# Chameleon-Mini-RevE-3.net
KiCad netlist of a schematic drawn in EAGLE
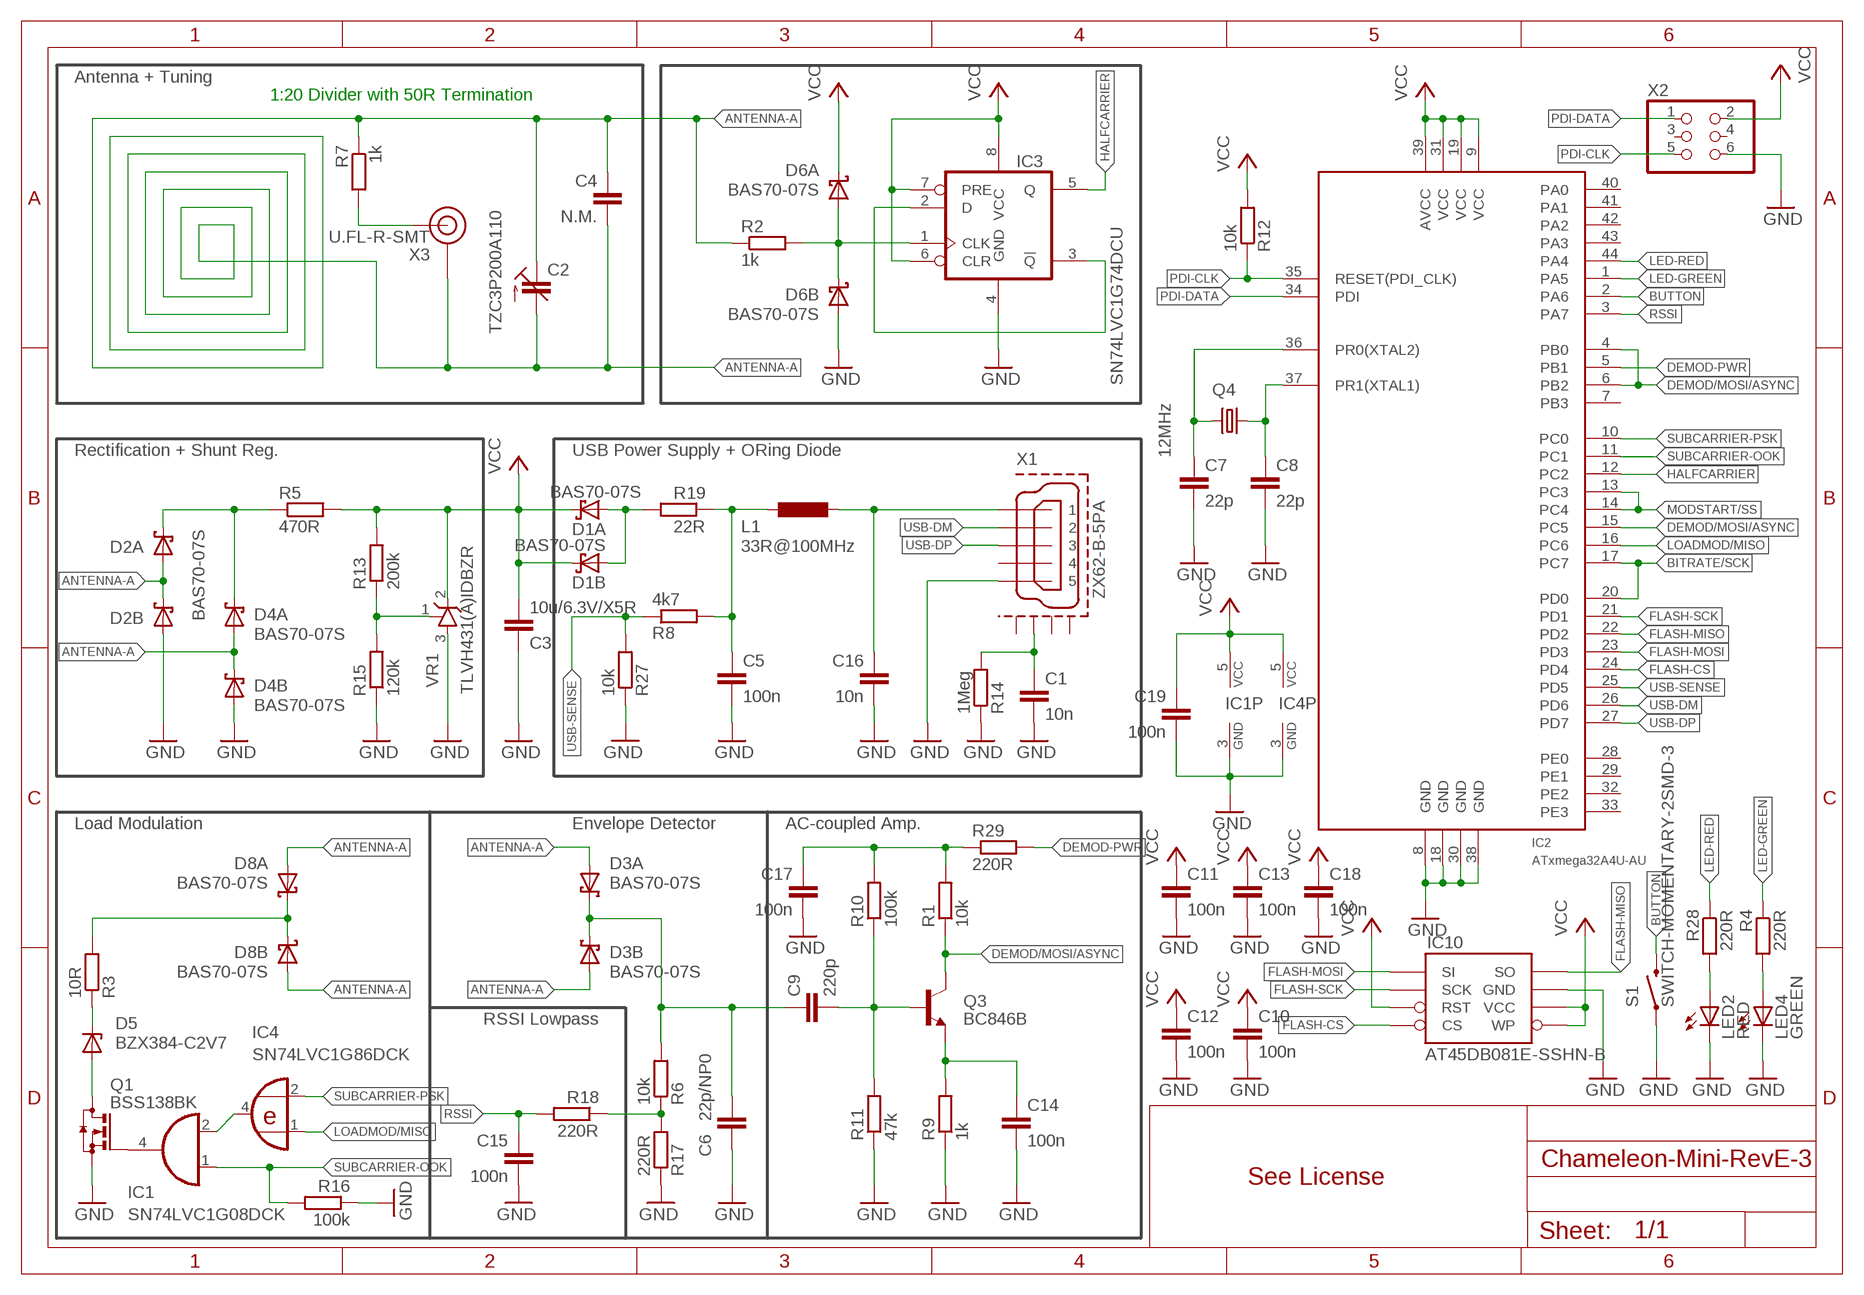
[diagram p0: schematic, sheet 1]

(export (version "E")
  (design (tool "Eeschema 10.0.6"))
  (components
    (comp (ref "C1")
      (value "10n")
      (footprint "eagle-import:C1206K")
      (libsource (lib "eagle-import") (part "C-EUC1206K"))
    )
    (comp (ref "C2")
      (value "TZC3P200A110")
      (footprint "eagle-import:TZC3P")
      (libsource (lib "eagle-import") (part "TZC3P"))
    )
    (comp (ref "C3")
      (value "10u/6.3V/X5R")
      (footprint "eagle-import:C1206K")
      (libsource (lib "eagle-import") (part "C-EUC1206K"))
    )
    (comp (ref "C4")
      (value "N.M.")
      (footprint "eagle-import:C1206")
      (libsource (lib "eagle-import") (part "C-EUC1206"))
    )
    (comp (ref "C5")
      (value "100n")
      (footprint "eagle-import:C1206K")
      (libsource (lib "eagle-import") (part "C-EUC1206K"))
    )
    (comp (ref "C6")
      (value "22p/NP0")
      (footprint "eagle-import:C0603K")
      (libsource (lib "eagle-import") (part "C-EUC0603K"))
    )
    (comp (ref "C7")
      (value "22p")
      (footprint "eagle-import:C0603K")
      (libsource (lib "eagle-import") (part "C-EUC0603K"))
    )
    (comp (ref "C8")
      (value "22p")
      (footprint "eagle-import:C0603K")
      (libsource (lib "eagle-import") (part "C-EUC0603K"))
    )
    (comp (ref "C9")
      (value "220p")
      (footprint "eagle-import:C0603K")
      (libsource (lib "eagle-import") (part "C-EUC0603K"))
    )
    (comp (ref "C10")
      (value "100n")
      (footprint "eagle-import:C0603K")
      (libsource (lib "eagle-import") (part "C-EUC0603K"))
    )
    (comp (ref "C11")
      (value "100n")
      (footprint "eagle-import:C0603K")
      (libsource (lib "eagle-import") (part "C-EUC0603K"))
    )
    (comp (ref "C12")
      (value "100n")
      (footprint "eagle-import:C0603K")
      (libsource (lib "eagle-import") (part "C-EUC0603K"))
    )
    (comp (ref "C13")
      (value "100n")
      (footprint "eagle-import:C0603K")
      (libsource (lib "eagle-import") (part "C-EUC0603K"))
    )
    (comp (ref "C14")
      (value "100n")
      (footprint "eagle-import:C0603K")
      (libsource (lib "eagle-import") (part "C-EUC0603K"))
    )
    (comp (ref "C15")
      (value "100n")
      (footprint "eagle-import:C0603K")
      (libsource (lib "eagle-import") (part "C-EUC0603K"))
    )
    (comp (ref "C16")
      (value "10n")
      (footprint "eagle-import:C1206K")
      (libsource (lib "eagle-import") (part "C-EUC1206K"))
    )
    (comp (ref "C17")
      (value "100n")
      (footprint "eagle-import:C0603K")
      (libsource (lib "eagle-import") (part "C-EUC0603K"))
    )
    (comp (ref "C18")
      (value "100n")
      (footprint "eagle-import:C0603K")
      (libsource (lib "eagle-import") (part "C-EUC0603K"))
    )
    (comp (ref "C19")
      (value "100n")
      (footprint "eagle-import:C0603K")
      (libsource (lib "eagle-import") (part "C-EUC0603K"))
    )
    (comp (ref "D1")
      (value "BAS70-07S")
      (footprint "eagle-import:SOT363_PHILIPS")
      (libsource (lib "eagle-import") (part "BAS70-07S"))
    )
    (comp (ref "D2")
      (value "BAS70-07S")
      (footprint "eagle-import:SOT363_PHILIPS")
      (libsource (lib "eagle-import") (part "BAS70-07S"))
    )
    (comp (ref "D3")
      (value "BAS70-07S")
      (footprint "eagle-import:SOT363_PHILIPS")
      (libsource (lib "eagle-import") (part "BAS70-07S"))
    )
    (comp (ref "D4")
      (value "BAS70-07S")
      (footprint "eagle-import:SOT363_PHILIPS")
      (libsource (lib "eagle-import") (part "BAS70-07S"))
    )
    (comp (ref "D5")
      (value "BZX384-C2V7")
      (footprint "eagle-import:SOD323")
      (libsource (lib "eagle-import") (part "BZX384"))
    )
    (comp (ref "D6")
      (value "BAS70-07S")
      (footprint "eagle-import:SOT363_PHILIPS")
      (libsource (lib "eagle-import") (part "BAS70-07S"))
    )
    (comp (ref "D8")
      (value "BAS70-07S")
      (footprint "eagle-import:SOT363_PHILIPS")
      (libsource (lib "eagle-import") (part "BAS70-07S"))
    )
    (comp (ref "IC1")
      (value "SN74LVC1G08DCK")
      (footprint "eagle-import:SC70-5")
      (libsource (lib "eagle-import") (part "741G08DCKLVC"))
    )
    (comp (ref "IC2")
      (value "ATxmega32A4U-AU")
      (footprint "eagle-import:TQFP44")
      (libsource (lib "eagle-import") (part "ATXMEGA_A4-A"))
    )
    (comp (ref "IC3")
      (value "SN74LVC1G74DCU")
      (footprint "eagle-import:VSSOP8")
      (libsource (lib "eagle-import") (part "74LVC1G74DC"))
    )
    (comp (ref "IC4")
      (value "SN74LVC1G86DCK")
      (footprint "eagle-import:SC70-5")
      (libsource (lib "eagle-import") (part "741G86DCKAHC"))
    )
    (comp (ref "IC10")
      (value "AT45DB081E-SSHN-B")
      (footprint "eagle-import:SO08")
      (libsource (lib "eagle-import") (part "AT45DB041B"))
    )
    (comp (ref "L1")
      (value "33R@100MHz")
      (footprint "eagle-import:L2012C")
      (libsource (lib "eagle-import") (part "L-EUL2012C"))
    )
    (comp (ref "LED2")
      (value "RED")
      (footprint "eagle-import:CHIPLED_0805")
      (libsource (lib "eagle-import") (part "LEDCHIPLED_0805"))
    )
    (comp (ref "LED4")
      (value "GREEN")
      (footprint "eagle-import:CHIPLED_0805")
      (libsource (lib "eagle-import") (part "LEDCHIPLED_0805"))
    )
    (comp (ref "Q1")
      (value "BSS138BK")
      (footprint "eagle-import:SOT23")
      (libsource (lib "eagle-import") (part "BSS123"))
    )
    (comp (ref "Q3")
      (value "BC846B")
      (footprint "eagle-import:SOT23")
      (libsource (lib "eagle-import") (part "BC846SMDB"))
    )
    (comp (ref "Q4")
      (value "12MHz")
      (footprint "eagle-import:5MMX3.2MM")
      (libsource (lib "eagle-import") (part "TXC7B"))
    )
    (comp (ref "R1")
      (value "10k")
      (footprint "eagle-import:R0603")
      (libsource (lib "eagle-import") (part "R-EU_R0603"))
    )
    (comp (ref "R2")
      (value "1k")
      (footprint "eagle-import:R0603")
      (libsource (lib "eagle-import") (part "R-EU_R0603"))
    )
    (comp (ref "R3")
      (value "10R")
      (footprint "eagle-import:R0603")
      (libsource (lib "eagle-import") (part "R-EU_R0603"))
    )
    (comp (ref "R4")
      (value "220R")
      (footprint "eagle-import:R0603")
      (libsource (lib "eagle-import") (part "R-EU_R0603"))
    )
    (comp (ref "R5")
      (value "470R")
      (footprint "eagle-import:R1206")
      (libsource (lib "eagle-import") (part "R-EU_R1206"))
    )
    (comp (ref "R6")
      (value "10k")
      (footprint "eagle-import:R0603")
      (libsource (lib "eagle-import") (part "R-EU_R0603"))
    )
    (comp (ref "R7")
      (value "1k")
      (footprint "eagle-import:R1206")
      (libsource (lib "eagle-import") (part "R-EU_R1206"))
    )
    (comp (ref "R8")
      (value "4k7")
      (footprint "eagle-import:R0603")
      (libsource (lib "eagle-import") (part "R-EU_R0603"))
    )
    (comp (ref "R9")
      (value "1k")
      (footprint "eagle-import:R0603")
      (libsource (lib "eagle-import") (part "R-EU_R0603"))
    )
    (comp (ref "R10")
      (value "100k")
      (footprint "eagle-import:R0603")
      (libsource (lib "eagle-import") (part "R-EU_R0603"))
    )
    (comp (ref "R11")
      (value "47k")
      (footprint "eagle-import:R0603")
      (libsource (lib "eagle-import") (part "R-EU_R0603"))
    )
    (comp (ref "R12")
      (value "10k")
      (footprint "eagle-import:R0603")
      (libsource (lib "eagle-import") (part "R-EU_R0603"))
    )
    (comp (ref "R13")
      (value "200k")
      (footprint "eagle-import:R0603")
      (libsource (lib "eagle-import") (part "R-EU_R0603"))
    )
    (comp (ref "R14")
      (value "1Meg")
      (footprint "eagle-import:R1206")
      (libsource (lib "eagle-import") (part "R-EU_R1206"))
    )
    (comp (ref "R15")
      (value "120k")
      (footprint "eagle-import:R0603")
      (libsource (lib "eagle-import") (part "R-EU_R0603"))
    )
    (comp (ref "R16")
      (value "100k")
      (footprint "eagle-import:R0603")
      (libsource (lib "eagle-import") (part "R-EU_R0603"))
    )
    (comp (ref "R17")
      (value "220R")
      (footprint "eagle-import:R0603")
      (libsource (lib "eagle-import") (part "R-EU_R0603"))
    )
    (comp (ref "R18")
      (value "220R")
      (footprint "eagle-import:R0603")
      (libsource (lib "eagle-import") (part "R-EU_R0603"))
    )
    (comp (ref "R19")
      (value "22R")
      (footprint "eagle-import:R1206")
      (libsource (lib "eagle-import") (part "R-EU_R1206"))
    )
    (comp (ref "R27")
      (value "10k")
      (footprint "eagle-import:R0603")
      (libsource (lib "eagle-import") (part "R-EU_R0603"))
    )
    (comp (ref "R28")
      (value "220R")
      (footprint "eagle-import:R0603")
      (libsource (lib "eagle-import") (part "R-EU_R0603"))
    )
    (comp (ref "R29")
      (value "220R")
      (footprint "eagle-import:R0603")
      (libsource (lib "eagle-import") (part "R-EU_R0603"))
    )
    (comp (ref "S1")
      (value "SWITCH-MOMENTARY-2SMD-3")
      (footprint "eagle-import:TACTILE_SWITCH_SMD-3")
      (libsource (lib "eagle-import") (part "SWITCH-MOMENTARY-2SMD-3"))
    )
    (comp (ref "VR1")
      (value "TLVH431(A)IDBZR")
      (footprint "eagle-import:SOT23")
      (libsource (lib "eagle-import") (part "TLVH431-SOT23"))
    )
    (comp (ref "X1")
      (value "ZX62-B-5PA")
      (footprint "eagle-import:ZX62-B-5PA-LONG")
      (libsource (lib "eagle-import") (part "ZX62-B-5PA-LONG"))
    )
    (comp (ref "X2")
      (value "PINHD-2X3-2.54-EDGE")
      (footprint "eagle-import:PINHD-2X3-2.54-EDGE")
      (libsource (lib "eagle-import") (part "PINHD-2X3-2.54-EDGE"))
    )
    (comp (ref "X3")
      (value "U.FL-R-SMT")
      (footprint "eagle-import:U.FL-R-SMT")
      (libsource (lib "eagle-import") (part "U.FL-R-SMT"))
    )
  )
  (nets
    (net (code "1") (name "ANTENNA-A") (class "Default")
      (node (ref "C2") (pin "1") (pinfunction "A_1") (pintype "passive"))
      (node (ref "C2") (pin "2") (pinfunction "E_2") (pintype "passive"))
      (node (ref "C4") (pin "1") (pinfunction "1_1") (pintype "passive"))
      (node (ref "C4") (pin "2") (pinfunction "2_2") (pintype "passive"))
      (node (ref "D2") (pin "1") (pinfunction "A_1") (pintype "passive"))
      (node (ref "D2") (pin "3") (pinfunction "C_3") (pintype "passive"))
      (node (ref "D3") (pin "1") (pinfunction "A_1") (pintype "passive"))
      (node (ref "D3") (pin "4") (pinfunction "A_4") (pintype "passive"))
      (node (ref "D4") (pin "1") (pinfunction "A_1") (pintype "passive"))
      (node (ref "D4") (pin "3") (pinfunction "C_3") (pintype "passive"))
      (node (ref "D8") (pin "1") (pinfunction "A_1") (pintype "passive"))
      (node (ref "D8") (pin "4") (pinfunction "A_4") (pintype "passive"))
      (node (ref "R2") (pin "1") (pinfunction "1_1") (pintype "passive"))
      (node (ref "R7") (pin "1") (pinfunction "1_1") (pintype "passive"))
      (node (ref "X3") (pin "GND2") (pinfunction "GND_GND2") (pintype "bidirectional"))
    )
    (net (code "2") (name "BITRATE{slash}SCK") (class "Default")
      (node (ref "IC2") (pin "17") (pinfunction "PC7_17") (pintype "bidirectional"))
      (node (ref "IC2") (pin "20") (pinfunction "PD0_20") (pintype "bidirectional"))
    )
    (net (code "3") (name "BUTTON") (class "Default")
      (node (ref "IC2") (pin "2") (pinfunction "PA6_2") (pintype "bidirectional"))
      (node (ref "S1") (pin "4") (pinfunction "2_4") (pintype "passive"))
    )
    (net (code "4") (name "DEMOD-PWR") (class "Default")
      (node (ref "IC2") (pin "5") (pinfunction "PB1_5") (pintype "bidirectional"))
      (node (ref "R29") (pin "2") (pinfunction "2_2") (pintype "passive"))
    )
    (net (code "5") (name "DEMOD{slash}MOSI{slash}ASYNC") (class "Default")
      (node (ref "IC2") (pin "15") (pinfunction "PC5_15") (pintype "bidirectional"))
      (node (ref "IC2") (pin "4") (pinfunction "PB0_4") (pintype "bidirectional"))
      (node (ref "IC2") (pin "6") (pinfunction "PB2_6") (pintype "bidirectional"))
      (node (ref "Q3") (pin "3") (pinfunction "C_3") (pintype "passive"))
      (node (ref "R1") (pin "1") (pinfunction "1_1") (pintype "passive"))
    )
    (net (code "6") (name "FLASH-CS") (class "Default")
      (node (ref "IC10") (pin "4") (pinfunction "CS_4") (pintype "bidirectional"))
      (node (ref "IC2") (pin "24") (pinfunction "PD4_24") (pintype "bidirectional"))
    )
    (net (code "7") (name "FLASH-MISO") (class "Default")
      (node (ref "IC10") (pin "8") (pinfunction "SO_8") (pintype "bidirectional"))
      (node (ref "IC2") (pin "22") (pinfunction "PD2_22") (pintype "bidirectional"))
    )
    (net (code "8") (name "FLASH-MOSI") (class "Default")
      (node (ref "IC10") (pin "1") (pinfunction "SI_1") (pintype "bidirectional"))
      (node (ref "IC2") (pin "23") (pinfunction "PD3_23") (pintype "bidirectional"))
    )
    (net (code "9") (name "FLASH-SCK") (class "Default")
      (node (ref "IC10") (pin "2") (pinfunction "SCK_2") (pintype "bidirectional"))
      (node (ref "IC2") (pin "21") (pinfunction "PD1_21") (pintype "bidirectional"))
    )
    (net (code "10") (name "GND") (class "Default")
      (node (ref "C1") (pin "2") (pinfunction "2_2") (pintype "passive"))
      (node (ref "C10") (pin "2") (pinfunction "2_2") (pintype "passive"))
      (node (ref "C11") (pin "2") (pinfunction "2_2") (pintype "passive"))
      (node (ref "C12") (pin "2") (pinfunction "2_2") (pintype "passive"))
      (node (ref "C13") (pin "2") (pinfunction "2_2") (pintype "passive"))
      (node (ref "C14") (pin "2") (pinfunction "2_2") (pintype "passive"))
      (node (ref "C15") (pin "2") (pinfunction "2_2") (pintype "passive"))
      (node (ref "C16") (pin "2") (pinfunction "2_2") (pintype "passive"))
      (node (ref "C17") (pin "2") (pinfunction "2_2") (pintype "passive"))
      (node (ref "C18") (pin "2") (pinfunction "2_2") (pintype "passive"))
      (node (ref "C19") (pin "2") (pinfunction "2_2") (pintype "passive"))
      (node (ref "C3") (pin "1") (pinfunction "1_1") (pintype "passive"))
      (node (ref "C5") (pin "2") (pinfunction "2_2") (pintype "passive"))
      (node (ref "C6") (pin "2") (pinfunction "2_2") (pintype "passive"))
      (node (ref "C7") (pin "2") (pinfunction "2_2") (pintype "passive"))
      (node (ref "C8") (pin "2") (pinfunction "2_2") (pintype "passive"))
      (node (ref "D2") (pin "4") (pinfunction "A_4") (pintype "passive"))
      (node (ref "D4") (pin "4") (pinfunction "A_4") (pintype "passive"))
      (node (ref "D6") (pin "4") (pinfunction "A_4") (pintype "passive"))
      (node (ref "IC1") (pin "3") (pinfunction "GND_3") (pintype "power_in"))
      (node (ref "IC10") (pin "7") (pinfunction "GND_7") (pintype "bidirectional"))
      (node (ref "IC2") (pin "18") (pinfunction "GND_18") (pintype "bidirectional"))
      (node (ref "IC2") (pin "30") (pinfunction "GND_30") (pintype "bidirectional"))
      (node (ref "IC2") (pin "38") (pinfunction "GND_38") (pintype "bidirectional"))
      (node (ref "IC2") (pin "8") (pinfunction "GND_8") (pintype "bidirectional"))
      (node (ref "IC3") (pin "4") (pinfunction "GND_4") (pintype "bidirectional"))
      (node (ref "IC4") (pin "3") (pinfunction "GND_3") (pintype "power_in"))
      (node (ref "LED2") (pin "C") (pinfunction "C_C") (pintype "passive"))
      (node (ref "LED4") (pin "C") (pinfunction "C_C") (pintype "passive"))
      (node (ref "Q1") (pin "2") (pinfunction "S_2") (pintype "passive"))
      (node (ref "R11") (pin "1") (pinfunction "1_1") (pintype "passive"))
      (node (ref "R14") (pin "1") (pinfunction "1_1") (pintype "passive"))
      (node (ref "R15") (pin "1") (pinfunction "1_1") (pintype "passive"))
      (node (ref "R16") (pin "1") (pinfunction "1_1") (pintype "passive"))
      (node (ref "R17") (pin "1") (pinfunction "1_1") (pintype "passive"))
      (node (ref "R27") (pin "1") (pinfunction "1_1") (pintype "passive"))
      (node (ref "R9") (pin "1") (pinfunction "1_1") (pintype "passive"))
      (node (ref "S1") (pin "1") (pinfunction "1_1") (pintype "passive"))
      (node (ref "VR1") (pin "3") (pinfunction "A_3") (pintype "passive"))
      (node (ref "X1") (pin "5") (pinfunction "5_5") (pintype "input"))
      (node (ref "X2") (pin "6") (pinfunction "6_6") (pintype "passive"))
    )
    (net (code "11") (name "HALFCARRIER") (class "Default")
      (node (ref "IC2") (pin "12") (pinfunction "PC2_12") (pintype "bidirectional"))
      (node (ref "IC3") (pin "5") (pinfunction "Q_5") (pintype "output"))
    )
    (net (code "12") (name "LED-GREEN") (class "Default")
      (node (ref "IC2") (pin "1") (pinfunction "PA5_1") (pintype "bidirectional"))
      (node (ref "R4") (pin "1") (pinfunction "1_1") (pintype "passive"))
    )
    (net (code "13") (name "LED-RED") (class "Default")
      (node (ref "IC2") (pin "44") (pinfunction "PA4_44") (pintype "bidirectional"))
      (node (ref "R28") (pin "1") (pinfunction "1_1") (pintype "passive"))
    )
    (net (code "14") (name "LOADMOD{slash}MISO") (class "Default")
      (node (ref "IC2") (pin "16") (pinfunction "PC6_16") (pintype "bidirectional"))
      (node (ref "IC4") (pin "1") (pinfunction "I0_1") (pintype "input"))
    )
    (net (code "15") (name "MODSTART{slash}SS") (class "Default")
      (node (ref "IC2") (pin "13") (pinfunction "PC3_13") (pintype "bidirectional"))
      (node (ref "IC2") (pin "14") (pinfunction "PC4_14") (pintype "bidirectional"))
    )
    (net (code "16") (name "Net-(C5-Pad1)") (class "Default")
      (node (ref "C5") (pin "1") (pinfunction "1_1") (pintype "passive"))
      (node (ref "L1") (pin "2") (pinfunction "2_2") (pintype "passive"))
      (node (ref "R19") (pin "1") (pinfunction "1_1") (pintype "passive"))
      (node (ref "R8") (pin "2") (pinfunction "2_2") (pintype "passive"))
    )
    (net (code "17") (name "Net-(C16-Pad1)") (class "Default")
      (node (ref "C16") (pin "1") (pinfunction "1_1") (pintype "passive"))
      (node (ref "L1") (pin "1") (pinfunction "1_1") (pintype "passive"))
      (node (ref "X1") (pin "1") (pinfunction "1_1") (pintype "input"))
    )
    (net (code "18") (name "Net-(C17-Pad1)") (class "Default")
      (node (ref "C17") (pin "1") (pinfunction "1_1") (pintype "passive"))
      (node (ref "R1") (pin "2") (pinfunction "2_2") (pintype "passive"))
      (node (ref "R10") (pin "2") (pinfunction "2_2") (pintype "passive"))
      (node (ref "R29") (pin "1") (pinfunction "1_1") (pintype "passive"))
    )
    (net (code "19") (name "Net-(D1A-A)") (class "Default")
      (node (ref "D1") (pin "1") (pinfunction "A_1") (pintype "passive"))
      (node (ref "D1") (pin "4") (pinfunction "A_4") (pintype "passive"))
      (node (ref "R19") (pin "2") (pinfunction "2_2") (pintype "passive"))
    )
    (net (code "20") (name "Net-(D2A-C)") (class "Default")
      (node (ref "D2") (pin "6") (pinfunction "C_6") (pintype "passive"))
      (node (ref "D4") (pin "6") (pinfunction "C_6") (pintype "passive"))
      (node (ref "R5") (pin "1") (pinfunction "1_1") (pintype "passive"))
    )
    (net (code "21") (name "Net-(D3A-C)") (class "Default")
      (node (ref "C6") (pin "1") (pinfunction "1_1") (pintype "passive"))
      (node (ref "C9") (pin "1") (pinfunction "1_1") (pintype "passive"))
      (node (ref "D3") (pin "3") (pinfunction "C_3") (pintype "passive"))
      (node (ref "D3") (pin "6") (pinfunction "C_6") (pintype "passive"))
      (node (ref "R6") (pin "2") (pinfunction "2_2") (pintype "passive"))
    )
    (net (code "22") (name "Net-(D5-A)") (class "Default")
      (node (ref "D5") (pin "2") (pinfunction "A_2") (pintype "passive"))
      (node (ref "Q1") (pin "3") (pinfunction "D_3") (pintype "passive"))
    )
    (net (code "23") (name "Net-(D5-C)") (class "Default")
      (node (ref "D5") (pin "1") (pinfunction "C_1") (pintype "passive"))
      (node (ref "R3") (pin "1") (pinfunction "1_1") (pintype "passive"))
    )
    (net (code "24") (name "Net-(D6A-A)") (class "Default")
      (node (ref "D6") (pin "1") (pinfunction "A_1") (pintype "passive"))
      (node (ref "D6") (pin "3") (pinfunction "C_3") (pintype "passive"))
      (node (ref "IC3") (pin "1") (pinfunction "CLK_1") (pintype "input"))
      (node (ref "R2") (pin "2") (pinfunction "2_2") (pintype "passive"))
    )
    (net (code "25") (name "Net-(D8A-C)") (class "Default")
      (node (ref "D8") (pin "3") (pinfunction "C_3") (pintype "passive"))
      (node (ref "D8") (pin "6") (pinfunction "C_6") (pintype "passive"))
      (node (ref "R3") (pin "2") (pinfunction "2_2") (pintype "passive"))
    )
    (net (code "26") (name "Net-(IC1A-I1)") (class "Default")
      (node (ref "IC1") (pin "2") (pinfunction "I1_2") (pintype "input"))
      (node (ref "IC4") (pin "4") (pinfunction "O_4") (pintype "output"))
    )
    (net (code "27") (name "Net-(IC1A-O)") (class "Default")
      (node (ref "IC1") (pin "4") (pinfunction "O_4") (pintype "output"))
      (node (ref "Q1") (pin "1") (pinfunction "G_1") (pintype "passive"))
    )
    (net (code "28") (name "Net-(IC2-PR0(XTAL2))") (class "Default")
      (node (ref "C7") (pin "1") (pinfunction "1_1") (pintype "passive"))
      (node (ref "IC2") (pin "36") (pinfunction "PR0(XTAL2)_36") (pintype "bidirectional"))
      (node (ref "Q4") (pin "3") (pinfunction "2_3") (pintype "passive"))
    )
    (net (code "29") (name "Net-(IC2-PR1(XTAL1))") (class "Default")
      (node (ref "C8") (pin "1") (pinfunction "1_1") (pintype "passive"))
      (node (ref "IC2") (pin "37") (pinfunction "PR1(XTAL1)_37") (pintype "bidirectional"))
      (node (ref "Q4") (pin "1") (pinfunction "1_1") (pintype "passive"))
    )
    (net (code "30") (name "Net-(IC3-D)") (class "Default")
      (node (ref "IC3") (pin "2") (pinfunction "D_2") (pintype "input"))
      (node (ref "IC3") (pin "3") (pinfunction "~{Q}_3") (pintype "output"))
    )
    (net (code "31") (name "Net-(LED2-PadA)") (class "Default")
      (node (ref "LED2") (pin "A") (pinfunction "A_A") (pintype "passive"))
      (node (ref "R28") (pin "2") (pinfunction "2_2") (pintype "passive"))
    )
    (net (code "32") (name "Net-(LED4-PadA)") (class "Default")
      (node (ref "LED4") (pin "A") (pinfunction "A_A") (pintype "passive"))
      (node (ref "R4") (pin "2") (pinfunction "2_2") (pintype "passive"))
    )
    (net (code "33") (name "Net-(Q3-B)") (class "Default")
      (node (ref "C9") (pin "2") (pinfunction "2_2") (pintype "passive"))
      (node (ref "Q3") (pin "1") (pinfunction "B_1") (pintype "passive"))
      (node (ref "R10") (pin "1") (pinfunction "1_1") (pintype "passive"))
      (node (ref "R11") (pin "2") (pinfunction "2_2") (pintype "passive"))
    )
    (net (code "34") (name "Net-(Q3-E)") (class "Default")
      (node (ref "C14") (pin "1") (pinfunction "1_1") (pintype "passive"))
      (node (ref "Q3") (pin "2") (pinfunction "E_2") (pintype "passive"))
      (node (ref "R9") (pin "2") (pinfunction "2_2") (pintype "passive"))
    )
    (net (code "35") (name "Net-(R7-Pad2)") (class "Default")
      (node (ref "R7") (pin "2") (pinfunction "2_2") (pintype "passive"))
      (node (ref "X3") (pin "SIG") (pinfunction "SIG_SIG") (pintype "bidirectional"))
    )
    (net (code "36") (name "Net-(R17-Pad2)") (class "Default")
      (node (ref "R17") (pin "2") (pinfunction "2_2") (pintype "passive"))
      (node (ref "R18") (pin "1") (pinfunction "1_1") (pintype "passive"))
      (node (ref "R6") (pin "1") (pinfunction "1_1") (pintype "passive"))
    )
    (net (code "37") (name "Net-(VR1-R)") (class "Default")
      (node (ref "R13") (pin "1") (pinfunction "1_1") (pintype "passive"))
      (node (ref "R15") (pin "2") (pinfunction "2_2") (pintype "passive"))
      (node (ref "VR1") (pin "1") (pinfunction "R_1") (pintype "passive"))
    )
    (net (code "38") (name "Net-(X1-GND2)") (class "Default")
      (node (ref "C1") (pin "1") (pinfunction "1_1") (pintype "passive"))
      (node (ref "R14") (pin "2") (pinfunction "2_2") (pintype "passive"))
      (node (ref "X1") (pin "P$2") (pinfunction "GND2_P$2") (pintype "bidirectional"))
    )
    (net (code "39") (name "PDI-CLK") (class "Default")
      (node (ref "IC2") (pin "35") (pinfunction "RESET(PDI_CLK)_35") (pintype "bidirectional"))
      (node (ref "R12") (pin "1") (pinfunction "1_1") (pintype "passive"))
      (node (ref "X2") (pin "5") (pinfunction "5_5") (pintype "passive"))
    )
    (net (code "40") (name "PDI-DATA") (class "Default")
      (node (ref "IC2") (pin "34") (pinfunction "PDI_34") (pintype "bidirectional"))
      (node (ref "X2") (pin "1") (pinfunction "1_1") (pintype "passive"))
    )
    (net (code "41") (name "RSSI") (class "Default")
      (node (ref "C15") (pin "1") (pinfunction "1_1") (pintype "passive"))
      (node (ref "IC2") (pin "3") (pinfunction "PA7_3") (pintype "bidirectional"))
      (node (ref "R18") (pin "2") (pinfunction "2_2") (pintype "passive"))
    )
    (net (code "42") (name "SUBCARRIER-OOK") (class "Default")
      (node (ref "IC1") (pin "1") (pinfunction "I0_1") (pintype "input"))
      (node (ref "IC2") (pin "11") (pinfunction "PC1_11") (pintype "bidirectional"))
      (node (ref "R16") (pin "2") (pinfunction "2_2") (pintype "passive"))
    )
    (net (code "43") (name "SUBCARRIER-PSK") (class "Default")
      (node (ref "IC2") (pin "10") (pinfunction "PC0_10") (pintype "bidirectional"))
      (node (ref "IC4") (pin "2") (pinfunction "I1_2") (pintype "input"))
    )
    (net (code "44") (name "USB-DM") (class "Default")
      (node (ref "IC2") (pin "26") (pinfunction "PD6_26") (pintype "bidirectional"))
      (node (ref "X1") (pin "2") (pinfunction "2_2") (pintype "input"))
    )
    (net (code "45") (name "USB-DP") (class "Default")
      (node (ref "IC2") (pin "27") (pinfunction "PD7_27") (pintype "bidirectional"))
      (node (ref "X1") (pin "3") (pinfunction "3_3") (pintype "input"))
    )
    (net (code "46") (name "USB-SENSE") (class "Default")
      (node (ref "IC2") (pin "25") (pinfunction "PD5_25") (pintype "bidirectional"))
      (node (ref "R27") (pin "2") (pinfunction "2_2") (pintype "passive"))
      (node (ref "R8") (pin "1") (pinfunction "1_1") (pintype "passive"))
    )
    (net (code "47") (name "VCC") (class "Default")
      (node (ref "C10") (pin "1") (pinfunction "1_1") (pintype "passive"))
      (node (ref "C11") (pin "1") (pinfunction "1_1") (pintype "passive"))
      (node (ref "C12") (pin "1") (pinfunction "1_1") (pintype "passive"))
      (node (ref "C13") (pin "1") (pinfunction "1_1") (pintype "passive"))
      (node (ref "C18") (pin "1") (pinfunction "1_1") (pintype "passive"))
      (node (ref "C19") (pin "1") (pinfunction "1_1") (pintype "passive"))
      (node (ref "C3") (pin "2") (pinfunction "2_2") (pintype "passive"))
      (node (ref "D1") (pin "3") (pinfunction "C_3") (pintype "passive"))
      (node (ref "D1") (pin "6") (pinfunction "C_6") (pintype "passive"))
      (node (ref "D6") (pin "6") (pinfunction "C_6") (pintype "passive"))
      (node (ref "IC1") (pin "5") (pinfunction "VCC_5") (pintype "power_in"))
      (node (ref "IC10") (pin "3") (pinfunction "RST_3") (pintype "bidirectional"))
      (node (ref "IC10") (pin "5") (pinfunction "WP_5") (pintype "bidirectional"))
      (node (ref "IC10") (pin "6") (pinfunction "VCC_6") (pintype "bidirectional"))
      (node (ref "IC2") (pin "19") (pinfunction "VCC_19") (pintype "bidirectional"))
      (node (ref "IC2") (pin "31") (pinfunction "VCC_31") (pintype "bidirectional"))
      (node (ref "IC2") (pin "39") (pinfunction "AVCC_39") (pintype "bidirectional"))
      (node (ref "IC2") (pin "9") (pinfunction "VCC_9") (pintype "bidirectional"))
      (node (ref "IC3") (pin "6") (pinfunction "CLR_6") (pintype "input"))
      (node (ref "IC3") (pin "7") (pinfunction "PRE_7") (pintype "input"))
      (node (ref "IC3") (pin "8") (pinfunction "VCC_8") (pintype "bidirectional"))
      (node (ref "IC4") (pin "5") (pinfunction "VCC_5") (pintype "power_in"))
      (node (ref "R12") (pin "2") (pinfunction "2_2") (pintype "passive"))
      (node (ref "R13") (pin "2") (pinfunction "2_2") (pintype "passive"))
      (node (ref "R5") (pin "2") (pinfunction "2_2") (pintype "passive"))
      (node (ref "VR1") (pin "2") (pinfunction "C_2") (pintype "passive"))
      (node (ref "X2") (pin "2") (pinfunction "2_2") (pintype "passive"))
    )
    (net (code "48") (name "unconnected-(IC2-PA0-Pad40)") (class "Default")
      (node (ref "IC2") (pin "40") (pinfunction "PA0_40") (pintype "bidirectional"))
    )
    (net (code "49") (name "unconnected-(IC2-PA1-Pad41)") (class "Default")
      (node (ref "IC2") (pin "41") (pinfunction "PA1_41") (pintype "bidirectional"))
    )
    (net (code "50") (name "unconnected-(IC2-PA2-Pad42)") (class "Default")
      (node (ref "IC2") (pin "42") (pinfunction "PA2_42") (pintype "bidirectional"))
    )
    (net (code "51") (name "unconnected-(IC2-PA3-Pad43)") (class "Default")
      (node (ref "IC2") (pin "43") (pinfunction "PA3_43") (pintype "bidirectional"))
    )
    (net (code "52") (name "unconnected-(IC2-PB3-Pad7)") (class "Default")
      (node (ref "IC2") (pin "7") (pinfunction "PB3_7") (pintype "bidirectional"))
    )
    (net (code "53") (name "unconnected-(IC2-PE0-Pad28)") (class "Default")
      (node (ref "IC2") (pin "28") (pinfunction "PE0_28") (pintype "bidirectional"))
    )
    (net (code "54") (name "unconnected-(IC2-PE1-Pad29)") (class "Default")
      (node (ref "IC2") (pin "29") (pinfunction "PE1_29") (pintype "bidirectional"))
    )
    (net (code "55") (name "unconnected-(IC2-PE2-Pad32)") (class "Default")
      (node (ref "IC2") (pin "32") (pinfunction "PE2_32") (pintype "bidirectional"))
    )
    (net (code "56") (name "unconnected-(IC2-PE3-Pad33)") (class "Default")
      (node (ref "IC2") (pin "33") (pinfunction "PE3_33") (pintype "bidirectional"))
    )
    (net (code "57") (name "unconnected-(X1-GND1-PadP$1)") (class "Default")
      (node (ref "X1") (pin "P$1") (pinfunction "GND1_P$1") (pintype "bidirectional"))
    )
    (net (code "58") (name "unconnected-(X1-GND3-PadP$6)") (class "Default")
      (node (ref "X1") (pin "P$6") (pinfunction "GND3_P$6") (pintype "bidirectional"))
    )
    (net (code "59") (name "unconnected-(X1-GND4-PadP$5)") (class "Default")
      (node (ref "X1") (pin "P$5") (pinfunction "GND4_P$5") (pintype "bidirectional"))
    )
    (net (code "60") (name "unconnected-(X1-Pad4)") (class "Default")
      (node (ref "X1") (pin "4") (pinfunction "4_4") (pintype "input"))
    )
    (net (code "61") (name "unconnected-(X2-Pad3)") (class "Default")
      (node (ref "X2") (pin "3") (pinfunction "3_3") (pintype "passive"))
    )
    (net (code "62") (name "unconnected-(X2-Pad4)") (class "Default")
      (node (ref "X2") (pin "4") (pinfunction "4_4") (pintype "passive"))
    )
    (net (code "63") (name "unconnected-(X3-GND-PadGND1)") (class "Default")
      (node (ref "X3") (pin "GND1") (pinfunction "GND_GND1") (pintype "bidirectional"))
    )
  )
)
